# design.net
KiCad netlist of a schematic drawn in Altium Designer
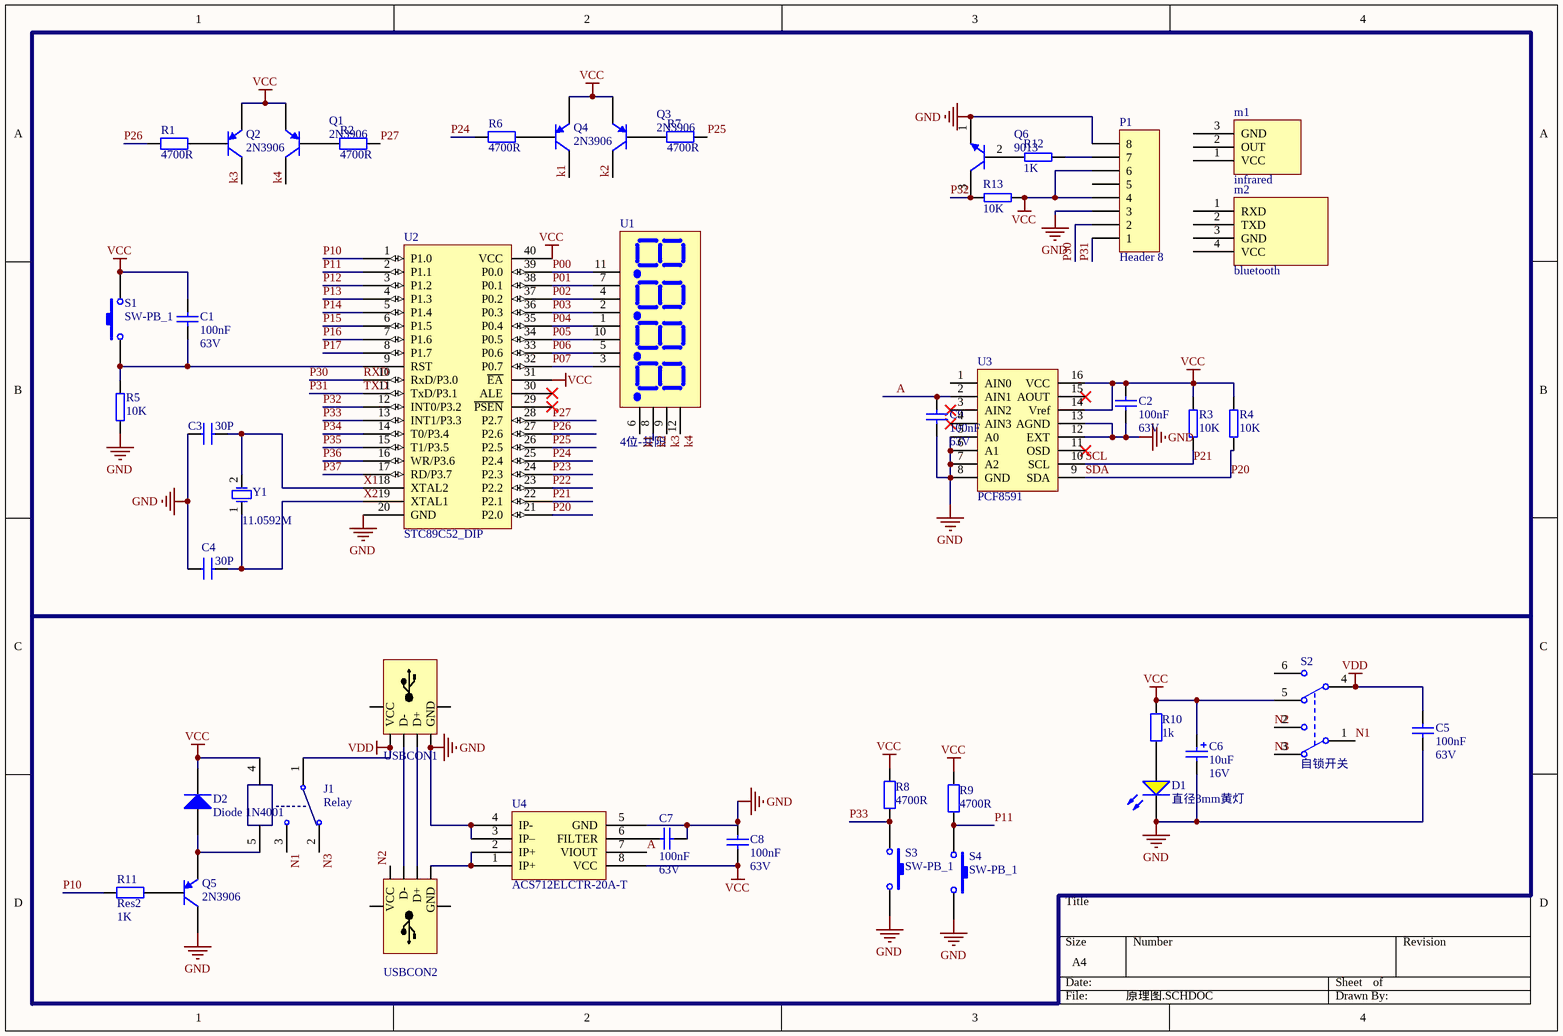
[diagram p0: 原理图.SCHDOC]

(export (version "E")
  (design (tool "Eeschema 10.0.6"))
  (components
    (comp (ref "C1")
      (value "100nF")
      (footprint "Capacitor-Disk-Middle")
      (description "Capacitor")
      (fields
        (field (name "VOLTAGE") "63V")
        (field (name "Comment") "Cap Nicklon")
        (field (name "PUBLISHER") "Altium Limited")
      )
      (libsource (lib "03-EButterflyIntegratedLibrary") (part "Cap Nicklon"))
    )
    (comp (ref "C2")
      (value "100nF")
      (footprint "Capacitor-Disk-Middle")
      (description "Capacitor")
      (fields
        (field (name "VOLTAGE") "63V")
        (field (name "Comment") "Cap Nicklon")
        (field (name "PUBLISHER") "Altium Limited")
      )
      (libsource (lib "03-EButterflyIntegratedLibrary") (part "Cap Nicklon"))
    )
    (comp (ref "C3")
      (value "30P")
      (footprint "CAP-0.1")
      (description "无极性电容")
      (libsource (lib "参考") (part "CAP"))
    )
    (comp (ref "C4")
      (value "30P")
      (footprint "CAP-0.1")
      (description "无极性电容")
      (libsource (lib "参考") (part "CAP"))
    )
    (comp (ref "C5")
      (value "100nF")
      (footprint "Capacitor-Disk-Middle")
      (description "CBB聚乙烯薄膜电容")
      (fields
        (field (name "VOLTAGE") "63V")
        (field (name "Comment") "Cap Nicklon")
        (field (name "PUBLISHER") "Altium Limited")
      )
      (libsource (lib "02 Miscellaneous_Devices_ZSF_Library") (part "Cap Nicklon"))
    )
    (comp (ref "C6")
      (value "10uF")
      (footprint "CAPPR2-5X5")
      (description "Polarized Capacitor (Radial)")
      (fields
        (field (name "VOLTAGE") "16V")
        (field (name "Comment") "Cap Pol 2.5x6.3")
        (field (name "PUBLISHER") "Altium Limited")
      )
      (libsource (lib "03-EButterflyIntegratedLibrary") (part "Cap Pol 2.5x6.3"))
    )
    (comp (ref "C7")
      (value "100nF")
      (footprint "Capacitor-Disk-Middle")
      (description "CBB聚乙烯薄膜电容")
      (fields
        (field (name "VOLTAGE") "63V")
        (field (name "Comment") "Cap Nicklon")
        (field (name "PUBLISHER") "Altium Limited")
      )
      (libsource (lib "02 Miscellaneous_Devices_ZSF_Library") (part "Cap Nicklon"))
    )
    (comp (ref "C8")
      (value "100nF")
      (footprint "Capacitor-Disk-Middle")
      (description "CBB聚乙烯薄膜电容")
      (fields
        (field (name "VOLTAGE") "63V")
        (field (name "Comment") "Cap Nicklon")
        (field (name "PUBLISHER") "Altium Limited")
      )
      (libsource (lib "02 Miscellaneous_Devices_ZSF_Library") (part "Cap Nicklon"))
    )
    (comp (ref "C9")
      (value "100nF")
      (footprint "Capacitor-Disk-Middle")
      (description "Capacitor")
      (fields
        (field (name "VOLTAGE") "63V")
        (field (name "Comment") "Cap Nicklon")
        (field (name "PUBLISHER") "Altium Limited")
      )
      (libsource (lib "03-EButterflyIntegratedLibrary") (part "Cap Nicklon"))
    )
    (comp (ref "D1")
      (value "直径3mm黄灯")
      (footprint "LED_#3")
      (description "直径3mm的发光二极管")
      (libsource (lib "02 Miscellaneous_Devices_ZSF_Library") (part "LED_3#黄灯"))
    )
    (comp (ref "D2")
      (value "Diode 1N4001")
      (footprint "DO-41")
      (description "1 Amp General Purpose Rectifier")
      (fields (field (name "PUBLISHER") "Altium Limited"))
      (libsource (lib "Miscellaneous Devices") (part "Diode 1N4001"))
    )
    (comp (ref "J1")
      (value "Relay")
      (footprint "RELAY-5")
      (description "继电器-单刀双置")
      (libsource (lib "02 Miscellaneous_Devices_ZSF_Library") (part "Relay"))
    )
    (comp (ref "m1") (value "infrared") (footprint "infrared") (libsource (lib "Schlib1") (part "infrared")))
    (comp (ref "m2")
      (value "bluetooth")
      (footprint "bluetooth")
      (libsource (lib "Schlib1") (part "bluetooth"))
    )
    (comp (ref "P1")
      (value "Header 8")
      (footprint "HDR1X8")
      (description "Header, 8-Pin")
      (fields (field (name "PUBLISHER") "Altium Limited"))
      (libsource (lib "Miscellaneous Connectors") (part "Header 8"))
    )
    (comp (ref "Q1")
      (value "2N3906")
      (footprint "TO-92A")
      (description "PNP General Purpose Amplifier")
      (fields (field (name "PUBLISHER") "Altium Limited"))
      (libsource (lib "Miscellaneous Devices") (part "2N3906"))
    )
    (comp (ref "Q2")
      (value "2N3906")
      (footprint "TO-92A")
      (description "PNP General Purpose Amplifier")
      (fields (field (name "PUBLISHER") "Altium Limited"))
      (libsource (lib "Miscellaneous Devices") (part "2N3906"))
    )
    (comp (ref "Q3")
      (value "2N3906")
      (footprint "TO-92A")
      (description "PNP General Purpose Amplifier")
      (fields (field (name "PUBLISHER") "Altium Limited"))
      (libsource (lib "Miscellaneous Devices") (part "2N3906"))
    )
    (comp (ref "Q4")
      (value "2N3906")
      (footprint "TO-92A")
      (description "PNP General Purpose Amplifier")
      (fields (field (name "PUBLISHER") "Altium Limited"))
      (libsource (lib "Miscellaneous Devices") (part "2N3906"))
    )
    (comp (ref "Q5")
      (value "2N3906")
      (footprint "TO-92A")
      (description "PNP General Purpose Amplifier")
      (fields (field (name "PUBLISHER") "Altium Limited"))
      (libsource (lib "Miscellaneous Devices") (part "2N3906"))
    )
    (comp (ref "Q6")
      (value "9013")
      (footprint "TO-92-3L")
      (description "NPN型小功率三极管")
      (libsource (lib "02 Miscellaneous_Devices_ZSF_Library") (part "9013_TO-92"))
    )
    (comp (ref "R1")
      (value "4700R")
      (footprint "AXIAL-0.4")
      (description "Resistor 直插电阻 2W")
      (fields (field (name "PUBLISHER") "Altium Limited"))
      (libsource (lib "02 Miscellaneous_Devices_ZSF_Library") (part "Res2_2W"))
    )
    (comp (ref "R2")
      (value "4700R")
      (footprint "AXIAL-0.4")
      (description "Resistor 直插电阻 2W")
      (fields (field (name "PUBLISHER") "Altium Limited"))
      (libsource (lib "02 Miscellaneous_Devices_ZSF_Library") (part "Res2_2W"))
    )
    (comp (ref "R3")
      (value "10K")
      (footprint "AXIAL-0.4")
      (description "电阻")
      (libsource (lib "参考") (part "RES"))
    )
    (comp (ref "R4")
      (value "10K")
      (footprint "AXIAL-0.4")
      (description "电阻")
      (libsource (lib "参考") (part "RES"))
    )
    (comp (ref "R5")
      (value "10K")
      (footprint "AXIAL-0.4")
      (description "电阻")
      (libsource (lib "参考") (part "RES"))
    )
    (comp (ref "R6")
      (value "4700R")
      (footprint "AXIAL-0.4")
      (description "Resistor 直插电阻 2W")
      (fields (field (name "PUBLISHER") "Altium Limited"))
      (libsource (lib "02 Miscellaneous_Devices_ZSF_Library") (part "Res2_2W"))
    )
    (comp (ref "R7")
      (value "4700R")
      (footprint "AXIAL-0.4")
      (description "Resistor 直插电阻 2W")
      (fields (field (name "PUBLISHER") "Altium Limited"))
      (libsource (lib "02 Miscellaneous_Devices_ZSF_Library") (part "Res2_2W"))
    )
    (comp (ref "R8")
      (value "4700R")
      (footprint "AXIAL-0.4")
      (description "Resistor 直插电阻 2W")
      (fields (field (name "PUBLISHER") "Altium Limited"))
      (libsource (lib "") (part "Res2_2W_1"))
    )
    (comp (ref "R9")
      (value "4700R")
      (footprint "AXIAL-0.4")
      (description "Resistor 直插电阻 2W")
      (fields (field (name "PUBLISHER") "Altium Limited"))
      (libsource (lib "") (part "Res2_2W_1"))
    )
    (comp (ref "R10")
      (value "1k")
      (footprint "AXIAL-0.4")
      (description "Resistor 直插电阻 2W")
      (fields (field (name "PUBLISHER") "Altium Limited"))
      (libsource (lib "") (part "Res2_2W_2"))
    )
    (comp (ref "R11")
      (value "Res2")
      (footprint "AXIAL-0.4")
      (description "Resistor")
      (fields (field (name "ALTIUM_VALUE") "1K") (field (name "PUBLISHER") "Altium Limited"))
      (libsource (lib "Miscellaneous Devices") (part "Res2"))
    )
    (comp (ref "R12")
      (value "1K")
      (footprint "AXIAL-0.4")
      (description "电阻")
      (libsource (lib "参考") (part "RES"))
    )
    (comp (ref "R13")
      (value "10K")
      (footprint "AXIAL-0.4")
      (description "电阻")
      (libsource (lib "参考") (part "RES"))
    )
    (comp (ref "S1")
      (value "SW-PB_1")
      (footprint "BUTTON_6*6")
      (description "Switch")
      (fields (field (name "PUBLISHER") "Altium Limited"))
      (libsource (lib "02 Miscellaneous_Devices_ZSF_Library") (part "SW-PB_1"))
    )
    (comp (ref "S2")
      (value "自锁开关")
      (footprint "sw_8.5mm")
      (libsource (lib "02 Miscellaneous_Devices_ZSF_Library") (part "SW DPDT"))
    )
    (comp (ref "S3")
      (value "SW-PB_1")
      (footprint "BUTTON_6*6")
      (description "Switch")
      (fields (field (name "PUBLISHER") "Altium Limited"))
      (libsource (lib "02 Miscellaneous_Devices_ZSF_Library") (part "SW-PB_1"))
    )
    (comp (ref "S4")
      (value "SW-PB_1")
      (footprint "BUTTON_6*6")
      (description "Switch")
      (fields (field (name "PUBLISHER") "Altium Limited"))
      (libsource (lib "02 Miscellaneous_Devices_ZSF_Library") (part "SW-PB_1"))
    )
    (comp (ref "U1")
      (value "4位-共阳")
      (footprint "SEG4_3641")
      (description "4位一体共阳数码管 0.36英寸30mm*14mm*7.2mm")
      (libsource (lib "02 Miscellaneous_Devices_ZSF_Library") (part "4位-共阳"))
    )
    (comp (ref "U2")
      (value "STC89C52_DIP")
      (footprint "DIP-40")
      (libsource (lib "02 Miscellaneous_Devices_ZSF_Library") (part "STC89C52_DIP"))
    )
    (comp (ref "U3")
      (value "PCF8591")
      (footprint "SOIC-16_300mil")
      (description "PCF8591 AD采集芯片")
      (libsource (lib "参考") (part "PCF8591"))
    )
    (comp (ref "U4")
      (value "ACS712ELCTR-20A-T")
      (footprint "SOIC-8_150mil")
      (description "传感器")
      (libsource (lib "02 Miscellaneous_Devices_ZSF_Library") (part "ACS712ELCTR-20A-T"))
    )
    (comp (ref "USBCON1")
      (value "USB-4P")
      (footprint "USB-A")
      (description "USB CONNECTOR")
      (libsource (lib "03-EButterflyIntegratedLibrary") (part "USB-4P"))
    )
    (comp (ref "USBCON2")
      (value "USB-4P")
      (footprint "USB-A")
      (description "USB CONNECTOR")
      (libsource (lib "") (part "USB-4P_1"))
    )
    (comp (ref "Y1")
      (value "11.0592M")
      (footprint "cry卧式")
      (description "晶振")
      (libsource (lib "参考") (part "XTAL DIP"))
    )
  )
  (nets
    (net (code "1") (name "/A") (class "Default")
      (node (ref "C9") (pin "2") (pinfunction "2_2") (pintype "passive"))
      (node (ref "U3") (pin "2") (pinfunction "AIN1_2") (pintype "passive"))
      (node (ref "U4") (pin "7") (pinfunction "VIOUT_7") (pintype "passive"))
    )
    (net (code "2") (name "/N1") (class "Default")
      (node (ref "J1") (pin "3") (pinfunction "3_3") (pintype "power_in"))
      (node (ref "S2") (pin "1") (pinfunction "1_1") (pintype "passive"))
    )
    (net (code "3") (name "/N2") (class "Default")
      (node (ref "S2") (pin "2") (pinfunction "2_2") (pintype "passive"))
      (node (ref "USBCON2") (pin "1") (pinfunction "VCC_1") (pintype "passive"))
    )
    (net (code "4") (name "/N3") (class "Default")
      (node (ref "J1") (pin "2") (pinfunction "2_2") (pintype "power_in"))
      (node (ref "S2") (pin "3") (pinfunction "3_3") (pintype "passive"))
    )
    (net (code "5") (name "/P00") (class "Default")
      (node (ref "U1") (pin "11") (pinfunction "a_11") (pintype "passive"))
      (node (ref "U2") (pin "39") (pinfunction "P0.0_39") (pintype "bidirectional"))
    )
    (net (code "6") (name "/P01") (class "Default")
      (node (ref "U1") (pin "7") (pinfunction "b_7") (pintype "passive"))
      (node (ref "U2") (pin "38") (pinfunction "P0.1_38") (pintype "bidirectional"))
    )
    (net (code "7") (name "/P02") (class "Default")
      (node (ref "U1") (pin "4") (pinfunction "c_4") (pintype "passive"))
      (node (ref "U2") (pin "37") (pinfunction "P0.2_37") (pintype "bidirectional"))
    )
    (net (code "8") (name "/P03") (class "Default")
      (node (ref "U1") (pin "2") (pinfunction "d_2") (pintype "passive"))
      (node (ref "U2") (pin "36") (pinfunction "P0.3_36") (pintype "bidirectional"))
    )
    (net (code "9") (name "/P04") (class "Default")
      (node (ref "U1") (pin "1") (pinfunction "e_1") (pintype "passive"))
      (node (ref "U2") (pin "35") (pinfunction "P0.4_35") (pintype "bidirectional"))
    )
    (net (code "10") (name "/P05") (class "Default")
      (node (ref "U1") (pin "10") (pinfunction "f_10") (pintype "passive"))
      (node (ref "U2") (pin "34") (pinfunction "P0.5_34") (pintype "bidirectional"))
    )
    (net (code "11") (name "/P06") (class "Default")
      (node (ref "U1") (pin "5") (pinfunction "g_5") (pintype "passive"))
      (node (ref "U2") (pin "33") (pinfunction "P0.6_33") (pintype "bidirectional"))
    )
    (net (code "12") (name "/P07") (class "Default")
      (node (ref "U1") (pin "3") (pinfunction "dp_3") (pintype "passive"))
      (node (ref "U2") (pin "32") (pinfunction "P0.7_32") (pintype "bidirectional"))
    )
    (net (code "13") (name "/P10") (class "Default")
      (node (ref "R11") (pin "1") (pinfunction "1_1") (pintype "passive"))
      (node (ref "U2") (pin "1") (pinfunction "P1.0_1") (pintype "bidirectional"))
    )
    (net (code "14") (name "/P11") (class "Default")
      (node (ref "R9") (pin "1") (pinfunction "1_1") (pintype "passive"))
      (node (ref "S4") (pin "1") (pinfunction "1_1") (pintype "passive"))
      (node (ref "U2") (pin "2") (pinfunction "P1.1_2") (pintype "bidirectional"))
    )
    (net (code "15") (name "/P12") (class "Default")
      (node (ref "U2") (pin "3") (pinfunction "P1.2_3") (pintype "bidirectional"))
    )
    (net (code "16") (name "/P13") (class "Default")
      (node (ref "U2") (pin "4") (pinfunction "P1.3_4") (pintype "bidirectional"))
    )
    (net (code "17") (name "/P14") (class "Default")
      (node (ref "U2") (pin "5") (pinfunction "P1.4_5") (pintype "bidirectional"))
    )
    (net (code "18") (name "/P15") (class "Default")
      (node (ref "U2") (pin "6") (pinfunction "P1.5_6") (pintype "bidirectional"))
    )
    (net (code "19") (name "/P16") (class "Default")
      (node (ref "U2") (pin "7") (pinfunction "P1.6_7") (pintype "bidirectional"))
    )
    (net (code "20") (name "/P17") (class "Default")
      (node (ref "U2") (pin "8") (pinfunction "P1.7_8") (pintype "bidirectional"))
    )
    (net (code "21") (name "/P20") (class "Default")
      (node (ref "R4") (pin "1") (pinfunction "1_1") (pintype "passive"))
      (node (ref "U2") (pin "21") (pinfunction "P2.0_21") (pintype "bidirectional"))
      (node (ref "U3") (pin "9") (pinfunction "SDA_9") (pintype "passive"))
    )
    (net (code "22") (name "/P21") (class "Default")
      (node (ref "R3") (pin "1") (pinfunction "1_1") (pintype "passive"))
      (node (ref "U2") (pin "22") (pinfunction "P2.1_22") (pintype "bidirectional"))
      (node (ref "U3") (pin "10") (pinfunction "SCL_10") (pintype "passive"))
    )
    (net (code "23") (name "/P22") (class "Default")
      (node (ref "U2") (pin "23") (pinfunction "P2.2_23") (pintype "bidirectional"))
    )
    (net (code "24") (name "/P23") (class "Default")
      (node (ref "U2") (pin "24") (pinfunction "P2.3_24") (pintype "bidirectional"))
    )
    (net (code "25") (name "/P24") (class "Default")
      (node (ref "R6") (pin "2") (pinfunction "2_2") (pintype "passive"))
      (node (ref "U2") (pin "25") (pinfunction "P2.4_25") (pintype "bidirectional"))
    )
    (net (code "26") (name "/P25") (class "Default")
      (node (ref "R7") (pin "1") (pinfunction "1_1") (pintype "passive"))
      (node (ref "U2") (pin "26") (pinfunction "P2.5_26") (pintype "bidirectional"))
    )
    (net (code "27") (name "/P26") (class "Default")
      (node (ref "R1") (pin "2") (pinfunction "2_2") (pintype "passive"))
      (node (ref "U2") (pin "27") (pinfunction "P2.6_27") (pintype "bidirectional"))
    )
    (net (code "28") (name "/P27") (class "Default")
      (node (ref "R2") (pin "1") (pinfunction "1_1") (pintype "passive"))
      (node (ref "U2") (pin "28") (pinfunction "P2.7_28") (pintype "bidirectional"))
    )
    (net (code "29") (name "/P30") (class "Default")
      (node (ref "P1") (pin "2") (pinfunction "2_2") (pintype "passive"))
      (node (ref "U2") (pin "10") (pinfunction "RxD/P3.0_10") (pintype "bidirectional"))
    )
    (net (code "30") (name "/P31") (class "Default")
      (node (ref "P1") (pin "1") (pinfunction "1_1") (pintype "passive"))
      (node (ref "U2") (pin "11") (pinfunction "TxD/P3.1_11") (pintype "bidirectional"))
    )
    (net (code "31") (name "/P32") (class "Default")
      (node (ref "Q6") (pin "3") (pinfunction "C_3") (pintype "passive"))
      (node (ref "R13") (pin "1") (pinfunction "1_1") (pintype "passive"))
      (node (ref "U2") (pin "12") (pinfunction "INT0/P3.2_12") (pintype "bidirectional"))
    )
    (net (code "32") (name "/P33") (class "Default")
      (node (ref "R8") (pin "1") (pinfunction "1_1") (pintype "passive"))
      (node (ref "S3") (pin "1") (pinfunction "1_1") (pintype "passive"))
      (node (ref "U2") (pin "13") (pinfunction "INT1/P3.3_13") (pintype "bidirectional"))
    )
    (net (code "33") (name "/P34") (class "Default")
      (node (ref "U2") (pin "14") (pinfunction "T0/P3.4_14") (pintype "bidirectional"))
    )
    (net (code "34") (name "/P35") (class "Default")
      (node (ref "U2") (pin "15") (pinfunction "T1/P3.5_15") (pintype "bidirectional"))
    )
    (net (code "35") (name "/P36") (class "Default")
      (node (ref "U2") (pin "16") (pinfunction "WR/P3.6_16") (pintype "bidirectional"))
    )
    (net (code "36") (name "/P37") (class "Default")
      (node (ref "U2") (pin "17") (pinfunction "RD/P3.7_17") (pintype "bidirectional"))
    )
    (net (code "37") (name "/X1") (class "Default")
      (node (ref "C3") (pin "2") (pinfunction "2_2") (pintype "passive"))
      (node (ref "U2") (pin "18") (pinfunction "XTAL2_18") (pintype "passive"))
      (node (ref "Y1") (pin "2") (pinfunction "OSC2_2") (pintype "passive"))
    )
    (net (code "38") (name "/X2") (class "Default")
      (node (ref "C4") (pin "2") (pinfunction "2_2") (pintype "passive"))
      (node (ref "U2") (pin "19") (pinfunction "XTAL1_19") (pintype "passive"))
      (node (ref "Y1") (pin "1") (pinfunction "OSC1_1") (pintype "passive"))
    )
    (net (code "39") (name "/k1") (class "Default")
      (node (ref "Q4") (pin "3") (pinfunction "C_3") (pintype "passive"))
      (node (ref "U1") (pin "6") (pinfunction "h1_6") (pintype "passive"))
    )
    (net (code "40") (name "/k2") (class "Default")
      (node (ref "Q3") (pin "3") (pinfunction "C_3") (pintype "passive"))
      (node (ref "U1") (pin "8") (pinfunction "h2_8") (pintype "passive"))
    )
    (net (code "41") (name "/k3") (class "Default")
      (node (ref "Q2") (pin "3") (pinfunction "C_3") (pintype "passive"))
      (node (ref "U1") (pin "9") (pinfunction "h3_9") (pintype "passive"))
    )
    (net (code "42") (name "/k4") (class "Default")
      (node (ref "Q1") (pin "3") (pinfunction "C_3") (pintype "passive"))
      (node (ref "U1") (pin "12") (pinfunction "h4_12") (pintype "passive"))
    )
    (net (code "43") (name "GND") (class "Default")
      (node (ref "C2") (pin "1") (pinfunction "1_1") (pintype "passive"))
      (node (ref "C3") (pin "1") (pinfunction "1_1") (pintype "passive"))
      (node (ref "C4") (pin "1") (pinfunction "1_1") (pintype "passive"))
      (node (ref "C5") (pin "2") (pinfunction "2_2") (pintype "passive"))
      (node (ref "C6") (pin "2") (pinfunction "2_2") (pintype "passive"))
      (node (ref "C7") (pin "2") (pinfunction "2_2") (pintype "passive"))
      (node (ref "C8") (pin "1") (pinfunction "1_1") (pintype "passive"))
      (node (ref "C9") (pin "1") (pinfunction "1_1") (pintype "passive"))
      (node (ref "D1") (pin "2") (pinfunction "2_2") (pintype "passive"))
      (node (ref "P1") (pin "3") (pinfunction "3_3") (pintype "passive"))
      (node (ref "P1") (pin "8") (pinfunction "8_8") (pintype "passive"))
      (node (ref "Q5") (pin "3") (pinfunction "C_3") (pintype "passive"))
      (node (ref "Q6") (pin "1") (pinfunction "E_1") (pintype "passive"))
      (node (ref "R5") (pin "1") (pinfunction "1_1") (pintype "passive"))
      (node (ref "S3") (pin "2") (pinfunction "2_2") (pintype "passive"))
      (node (ref "S4") (pin "2") (pinfunction "2_2") (pintype "passive"))
      (node (ref "U2") (pin "20") (pinfunction "GND_20") (pintype "power_in"))
      (node (ref "U3") (pin "12") (pinfunction "EXT_12") (pintype "passive"))
      (node (ref "U3") (pin "13") (pinfunction "AGND_13") (pintype "passive"))
      (node (ref "U3") (pin "5") (pinfunction "A0_5") (pintype "passive"))
      (node (ref "U3") (pin "6") (pinfunction "A1_6") (pintype "passive"))
      (node (ref "U3") (pin "7") (pinfunction "A2_7") (pintype "passive"))
      (node (ref "U3") (pin "8") (pinfunction "GND_8") (pintype "passive"))
      (node (ref "U4") (pin "3") (pinfunction "IP–_3") (pintype "passive"))
      (node (ref "U4") (pin "4") (pinfunction "IP-_4") (pintype "passive"))
      (node (ref "U4") (pin "5") (pinfunction "GND_5") (pintype "passive"))
      (node (ref "USBCON1") (pin "4") (pinfunction "GND_4") (pintype "passive"))
    )
    (net (code "44") (name "Net-(D1-Pad1)") (class "Default")
      (node (ref "D1") (pin "1") (pinfunction "1_1") (pintype "passive"))
      (node (ref "R10") (pin "1") (pinfunction "1_1") (pintype "passive"))
    )
    (net (code "45") (name "Net-(D2-A)") (class "Default")
      (node (ref "D2") (pin "1") (pinfunction "A_1") (pintype "passive"))
      (node (ref "J1") (pin "5") (pinfunction "5_5") (pintype "power_in"))
      (node (ref "Q5") (pin "1") (pinfunction "E_1") (pintype "passive"))
    )
    (net (code "46") (name "Net-(P1-Pad7)") (class "Default")
      (node (ref "P1") (pin "7") (pinfunction "7_7") (pintype "passive"))
      (node (ref "R12") (pin "2") (pinfunction "2_2") (pintype "passive"))
    )
    (net (code "47") (name "Net-(Q1-B)") (class "Default")
      (node (ref "Q1") (pin "2") (pinfunction "B_2") (pintype "passive"))
      (node (ref "R2") (pin "2") (pinfunction "2_2") (pintype "passive"))
    )
    (net (code "48") (name "Net-(Q2-B)") (class "Default")
      (node (ref "Q2") (pin "2") (pinfunction "B_2") (pintype "passive"))
      (node (ref "R1") (pin "1") (pinfunction "1_1") (pintype "passive"))
    )
    (net (code "49") (name "Net-(Q3-B)") (class "Default")
      (node (ref "Q3") (pin "2") (pinfunction "B_2") (pintype "passive"))
      (node (ref "R7") (pin "2") (pinfunction "2_2") (pintype "passive"))
    )
    (net (code "50") (name "Net-(Q4-B)") (class "Default")
      (node (ref "Q4") (pin "2") (pinfunction "B_2") (pintype "passive"))
      (node (ref "R6") (pin "1") (pinfunction "1_1") (pintype "passive"))
    )
    (net (code "51") (name "Net-(Q5-B)") (class "Default")
      (node (ref "Q5") (pin "2") (pinfunction "B_2") (pintype "passive"))
      (node (ref "R11") (pin "2") (pinfunction "2_2") (pintype "passive"))
    )
    (net (code "52") (name "Net-(Q6-B)") (class "Default")
      (node (ref "Q6") (pin "2") (pinfunction "B_2") (pintype "passive"))
      (node (ref "R12") (pin "1") (pinfunction "1_1") (pintype "passive"))
    )
    (net (code "53") (name "Net-(U2-RST)") (class "Default")
      (node (ref "C1") (pin "1") (pinfunction "1_1") (pintype "passive"))
      (node (ref "R5") (pin "2") (pinfunction "2_2") (pintype "passive"))
      (node (ref "S1") (pin "1") (pinfunction "1_1") (pintype "passive"))
      (node (ref "U2") (pin "9") (pinfunction "RST_9") (pintype "passive"))
    )
    (net (code "54") (name "Net-(U4-FILTER)") (class "Default")
      (node (ref "C7") (pin "1") (pinfunction "1_1") (pintype "passive"))
      (node (ref "U4") (pin "6") (pinfunction "FILTER_6") (pintype "passive"))
    )
    (net (code "55") (name "Net-(U4-IP+-Pad1)") (class "Default")
      (node (ref "U4") (pin "1") (pinfunction "IP+_1") (pintype "passive"))
      (node (ref "U4") (pin "2") (pinfunction "IP+_2") (pintype "passive"))
      (node (ref "USBCON2") (pin "4") (pinfunction "GND_4") (pintype "passive"))
    )
    (net (code "56") (name "Net-(USBCON1-D+)") (class "Default")
      (node (ref "USBCON1") (pin "3") (pinfunction "D+_3") (pintype "passive"))
      (node (ref "USBCON2") (pin "3") (pinfunction "D+_3") (pintype "passive"))
    )
    (net (code "57") (name "Net-(USBCON1-D-)") (class "Default")
      (node (ref "USBCON1") (pin "2") (pinfunction "D-_2") (pintype "passive"))
      (node (ref "USBCON2") (pin "2") (pinfunction "D-_2") (pintype "passive"))
    )
    (net (code "58") (name "VCC") (class "Default")
      (node (ref "C1") (pin "2") (pinfunction "2_2") (pintype "passive"))
      (node (ref "C2") (pin "2") (pinfunction "2_2") (pintype "passive"))
      (node (ref "C6") (pin "1") (pinfunction "1_1") (pintype "passive"))
      (node (ref "C8") (pin "2") (pinfunction "2_2") (pintype "passive"))
      (node (ref "D2") (pin "2") (pinfunction "K_2") (pintype "passive"))
      (node (ref "J1") (pin "4") (pinfunction "4_4") (pintype "power_in"))
      (node (ref "P1") (pin "4") (pinfunction "4_4") (pintype "passive"))
      (node (ref "P1") (pin "6") (pinfunction "6_6") (pintype "passive"))
      (node (ref "Q1") (pin "1") (pinfunction "E_1") (pintype "passive"))
      (node (ref "Q2") (pin "1") (pinfunction "E_1") (pintype "passive"))
      (node (ref "Q3") (pin "1") (pinfunction "E_1") (pintype "passive"))
      (node (ref "Q4") (pin "1") (pinfunction "E_1") (pintype "passive"))
      (node (ref "R10") (pin "2") (pinfunction "2_2") (pintype "passive"))
      (node (ref "R13") (pin "2") (pinfunction "2_2") (pintype "passive"))
      (node (ref "R3") (pin "2") (pinfunction "2_2") (pintype "passive"))
      (node (ref "R4") (pin "2") (pinfunction "2_2") (pintype "passive"))
      (node (ref "R8") (pin "2") (pinfunction "2_2") (pintype "passive"))
      (node (ref "R9") (pin "2") (pinfunction "2_2") (pintype "passive"))
      (node (ref "S1") (pin "2") (pinfunction "2_2") (pintype "passive"))
      (node (ref "S2") (pin "5") (pinfunction "5_5") (pintype "passive"))
      (node (ref "U2") (pin "31") (pinfunction "~{EA}_31") (pintype "passive"))
      (node (ref "U2") (pin "40") (pinfunction "VCC_40") (pintype "power_in"))
      (node (ref "U3") (pin "14") (pinfunction "Vref_14") (pintype "passive"))
      (node (ref "U3") (pin "16") (pinfunction "VCC_16") (pintype "passive"))
      (node (ref "U4") (pin "8") (pinfunction "VCC_8") (pintype "passive"))
    )
    (net (code "59") (name "VDD") (class "Default")
      (node (ref "C5") (pin "1") (pinfunction "1_1") (pintype "passive"))
      (node (ref "J1") (pin "1") (pinfunction "1_1") (pintype "power_in"))
      (node (ref "S2") (pin "4") (pinfunction "4_4") (pintype "passive"))
      (node (ref "USBCON1") (pin "1") (pinfunction "VCC_1") (pintype "passive"))
    )
    (net (code "60") (name "unconnected-(P1-Pad5)") (class "Default")
      (node (ref "P1") (pin "5") (pinfunction "5_5") (pintype "passive"))
    )
    (net (code "61") (name "unconnected-(S2-Pad6)") (class "Default")
      (node (ref "S2") (pin "6") (pinfunction "6_6") (pintype "passive"))
    )
    (net (code "62") (name "unconnected-(U2-ALE-Pad30)") (class "Default")
      (node (ref "U2") (pin "30") (pinfunction "ALE_30") (pintype "passive+no_connect"))
    )
    (net (code "63") (name "unconnected-(U2-~{PSEN}-Pad29)") (class "Default")
      (node (ref "U2") (pin "29") (pinfunction "~{PSEN}_29") (pintype "passive+no_connect"))
    )
    (net (code "64") (name "unconnected-(U3-AIN0-Pad1)") (class "Default")
      (node (ref "U3") (pin "1") (pinfunction "AIN0_1") (pintype "passive"))
    )
    (net (code "65") (name "unconnected-(U3-AIN2-Pad3)") (class "Default")
      (node (ref "U3") (pin "3") (pinfunction "AIN2_3") (pintype "passive+no_connect"))
    )
    (net (code "66") (name "unconnected-(U3-AIN3-Pad4)") (class "Default")
      (node (ref "U3") (pin "4") (pinfunction "AIN3_4") (pintype "passive+no_connect"))
    )
    (net (code "67") (name "unconnected-(U3-AOUT-Pad15)") (class "Default")
      (node (ref "U3") (pin "15") (pinfunction "AOUT_15") (pintype "passive+no_connect"))
    )
    (net (code "68") (name "unconnected-(U3-OSD-Pad11)") (class "Default")
      (node (ref "U3") (pin "11") (pinfunction "OSD_11") (pintype "passive+no_connect"))
    )
    (net (code "69") (name "unconnected-(USBCON1-GND-Pad5)") (class "Default")
      (node (ref "USBCON1") (pin "5") (pinfunction "GND_5") (pintype "passive"))
    )
    (net (code "70") (name "unconnected-(USBCON1-GND-Pad6)") (class "Default")
      (node (ref "USBCON1") (pin "6") (pinfunction "GND_6") (pintype "passive"))
    )
    (net (code "71") (name "unconnected-(USBCON2-GND-Pad5)") (class "Default")
      (node (ref "USBCON2") (pin "5") (pinfunction "GND_5") (pintype "passive"))
    )
    (net (code "72") (name "unconnected-(USBCON2-GND-Pad6)") (class "Default")
      (node (ref "USBCON2") (pin "6") (pinfunction "GND_6") (pintype "passive"))
    )
    (net (code "73") (name "unconnected-(m1-GND-Pad3)") (class "Default")
      (node (ref "m1") (pin "3") (pinfunction "GND_3") (pintype "passive"))
    )
    (net (code "74") (name "unconnected-(m1-OUT-Pad2)") (class "Default")
      (node (ref "m1") (pin "2") (pinfunction "OUT_2") (pintype "passive"))
    )
    (net (code "75") (name "unconnected-(m1-VCC-Pad1)") (class "Default")
      (node (ref "m1") (pin "1") (pinfunction "VCC_1") (pintype "passive"))
    )
    (net (code "76") (name "unconnected-(m2-GND-Pad3)") (class "Default")
      (node (ref "m2") (pin "3") (pinfunction "GND_3") (pintype "passive"))
    )
    (net (code "77") (name "unconnected-(m2-RXD-Pad1)") (class "Default")
      (node (ref "m2") (pin "1") (pinfunction "RXD_1") (pintype "passive"))
    )
    (net (code "78") (name "unconnected-(m2-TXD-Pad2)") (class "Default")
      (node (ref "m2") (pin "2") (pinfunction "TXD_2") (pintype "passive"))
    )
    (net (code "79") (name "unconnected-(m2-VCC-Pad4)") (class "Default")
      (node (ref "m2") (pin "4") (pinfunction "VCC_4") (pintype "passive"))
    )
  )
)
